# LEDs_-_Schematic.net
KiCad netlist of a schematic drawn in EAGLE
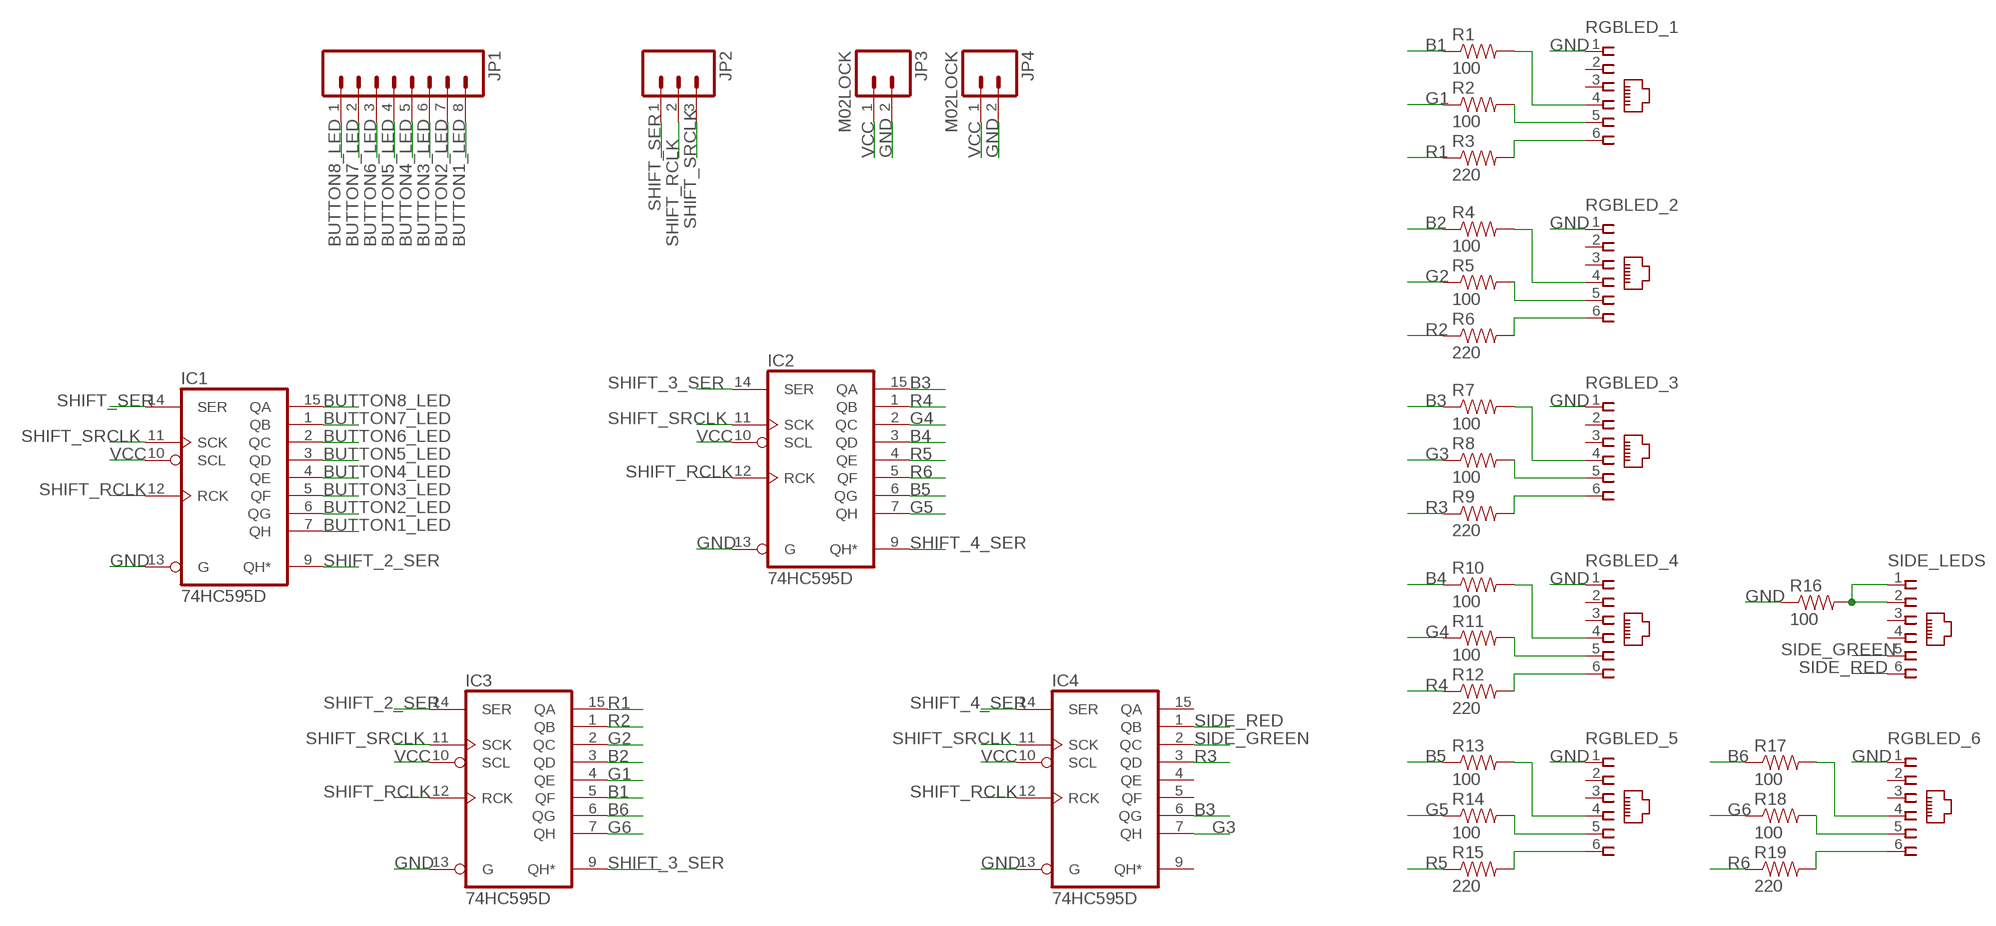
[diagram p0: schematic, sheet 1]

(export (version "E")
  (design (tool "Eeschema 10.0.6"))
  (components
    (comp (ref "IC1")
      (value "74HC595D")
      (footprint "eagle-import:SO16")
      (libsource (lib "eagle-import") (part "74595DHC"))
    )
    (comp (ref "IC2")
      (value "74HC595D")
      (footprint "eagle-import:SO16")
      (libsource (lib "eagle-import") (part "74595DHC"))
    )
    (comp (ref "IC3")
      (value "74HC595D")
      (footprint "eagle-import:SO16")
      (libsource (lib "eagle-import") (part "74595DHC"))
    )
    (comp (ref "IC4")
      (value "74HC595D")
      (footprint "eagle-import:SO16")
      (libsource (lib "eagle-import") (part "74595DHC"))
    )
    (comp (ref "JP1")
      (value "M08LOCK")
      (footprint "eagle-import:1X08_LOCK")
      (libsource (lib "eagle-import") (part "M08LOCK"))
    )
    (comp (ref "JP2")
      (value "M03LOCK")
      (footprint "eagle-import:1X03_LOCK")
      (libsource (lib "eagle-import") (part "M03LOCK"))
    )
    (comp (ref "JP3")
      (value "M02LOCK")
      (footprint "eagle-import:1X02_LOCK")
      (libsource (lib "eagle-import") (part "M02LOCK"))
    )
    (comp (ref "JP4")
      (value "M02LOCK")
      (footprint "eagle-import:1X02_LOCK")
      (libsource (lib "eagle-import") (part "M02LOCK"))
    )
    (comp (ref "R1")
      (value "100")
      (footprint "eagle-import:0603-RES")
      (libsource (lib "eagle-import") (part "RESISTOR0603"))
    )
    (comp (ref "R2")
      (value "100")
      (footprint "eagle-import:0603-RES")
      (libsource (lib "eagle-import") (part "RESISTOR0603"))
    )
    (comp (ref "R3")
      (value "220")
      (footprint "eagle-import:0603-RES")
      (libsource (lib "eagle-import") (part "RESISTOR0603"))
    )
    (comp (ref "R4")
      (value "100")
      (footprint "eagle-import:0603-RES")
      (libsource (lib "eagle-import") (part "RESISTOR0603"))
    )
    (comp (ref "R5")
      (value "100")
      (footprint "eagle-import:0603-RES")
      (libsource (lib "eagle-import") (part "RESISTOR0603"))
    )
    (comp (ref "R6")
      (value "220")
      (footprint "eagle-import:0603-RES")
      (libsource (lib "eagle-import") (part "RESISTOR0603"))
    )
    (comp (ref "R7")
      (value "100")
      (footprint "eagle-import:0603-RES")
      (libsource (lib "eagle-import") (part "RESISTOR0603"))
    )
    (comp (ref "R8")
      (value "100")
      (footprint "eagle-import:0603-RES")
      (libsource (lib "eagle-import") (part "RESISTOR0603"))
    )
    (comp (ref "R9")
      (value "220")
      (footprint "eagle-import:0603-RES")
      (libsource (lib "eagle-import") (part "RESISTOR0603"))
    )
    (comp (ref "R10")
      (value "100")
      (footprint "eagle-import:0603-RES")
      (libsource (lib "eagle-import") (part "RESISTOR0603"))
    )
    (comp (ref "R11")
      (value "100")
      (footprint "eagle-import:0603-RES")
      (libsource (lib "eagle-import") (part "RESISTOR0603"))
    )
    (comp (ref "R12")
      (value "220")
      (footprint "eagle-import:0603-RES")
      (libsource (lib "eagle-import") (part "RESISTOR0603"))
    )
    (comp (ref "R13")
      (value "100")
      (footprint "eagle-import:0603-RES")
      (libsource (lib "eagle-import") (part "RESISTOR0603"))
    )
    (comp (ref "R14")
      (value "100")
      (footprint "eagle-import:0603-RES")
      (libsource (lib "eagle-import") (part "RESISTOR0603"))
    )
    (comp (ref "R15")
      (value "220")
      (footprint "eagle-import:0603-RES")
      (libsource (lib "eagle-import") (part "RESISTOR0603"))
    )
    (comp (ref "R16")
      (value "100")
      (footprint "eagle-import:0603-RES")
      (libsource (lib "eagle-import") (part "RESISTOR0603"))
    )
    (comp (ref "R17")
      (value "100")
      (footprint "eagle-import:0603-RES")
      (libsource (lib "eagle-import") (part "RESISTOR0603"))
    )
    (comp (ref "R18")
      (value "100")
      (footprint "eagle-import:0603-RES")
      (libsource (lib "eagle-import") (part "RESISTOR0603"))
    )
    (comp (ref "R19")
      (value "220")
      (footprint "eagle-import:0603-RES")
      (libsource (lib "eagle-import") (part "RESISTOR0603"))
    )
    (comp (ref "RGBLED_1")
      (value "555165-1")
      (footprint "eagle-import:555165-1")
      (libsource (lib "eagle-import") (part "555165-1"))
    )
    (comp (ref "RGBLED_2")
      (value "555165-1")
      (footprint "eagle-import:555165-1")
      (libsource (lib "eagle-import") (part "555165-1"))
    )
    (comp (ref "RGBLED_3")
      (value "555165-1")
      (footprint "eagle-import:555165-1")
      (libsource (lib "eagle-import") (part "555165-1"))
    )
    (comp (ref "RGBLED_4")
      (value "555165-1")
      (footprint "eagle-import:555165-1")
      (libsource (lib "eagle-import") (part "555165-1"))
    )
    (comp (ref "RGBLED_5")
      (value "555165-1")
      (footprint "eagle-import:555165-1")
      (libsource (lib "eagle-import") (part "555165-1"))
    )
    (comp (ref "RGBLED_6")
      (value "555165-1")
      (footprint "eagle-import:555165-1")
      (libsource (lib "eagle-import") (part "555165-1"))
    )
    (comp (ref "SIDE_LEDS")
      (value "555165-1")
      (footprint "eagle-import:555165-1")
      (libsource (lib "eagle-import") (part "555165-1"))
    )
  )
  (nets
    (net (code "1") (name "/B1") (class "Default")
      (node (ref "IC3") (pin "5") (pinfunction "QF_5") (pintype "tri_state"))
      (node (ref "R1") (pin "1") (pinfunction "1_1") (pintype "passive"))
    )
    (net (code "2") (name "/B2") (class "Default")
      (node (ref "IC3") (pin "3") (pinfunction "QD_3") (pintype "tri_state"))
      (node (ref "R4") (pin "1") (pinfunction "1_1") (pintype "passive"))
    )
    (net (code "3") (name "/B3") (class "Default")
      (node (ref "IC2") (pin "15") (pinfunction "QA_15") (pintype "tri_state"))
      (node (ref "IC4") (pin "6") (pinfunction "QG_6") (pintype "tri_state"))
      (node (ref "R7") (pin "1") (pinfunction "1_1") (pintype "passive"))
    )
    (net (code "4") (name "/B4") (class "Default")
      (node (ref "IC2") (pin "3") (pinfunction "QD_3") (pintype "tri_state"))
      (node (ref "R10") (pin "1") (pinfunction "1_1") (pintype "passive"))
    )
    (net (code "5") (name "/B5") (class "Default")
      (node (ref "IC2") (pin "6") (pinfunction "QG_6") (pintype "tri_state"))
      (node (ref "R13") (pin "1") (pinfunction "1_1") (pintype "passive"))
    )
    (net (code "6") (name "/B6") (class "Default")
      (node (ref "IC3") (pin "6") (pinfunction "QG_6") (pintype "tri_state"))
      (node (ref "R17") (pin "1") (pinfunction "1_1") (pintype "passive"))
    )
    (net (code "7") (name "/BUTTON1_LED") (class "Default")
      (node (ref "IC1") (pin "7") (pinfunction "QH_7") (pintype "tri_state"))
      (node (ref "JP1") (pin "8") (pinfunction "8_8") (pintype "passive"))
    )
    (net (code "8") (name "/BUTTON2_LED") (class "Default")
      (node (ref "IC1") (pin "6") (pinfunction "QG_6") (pintype "tri_state"))
      (node (ref "JP1") (pin "7") (pinfunction "7_7") (pintype "passive"))
    )
    (net (code "9") (name "/BUTTON3_LED") (class "Default")
      (node (ref "IC1") (pin "5") (pinfunction "QF_5") (pintype "tri_state"))
      (node (ref "JP1") (pin "6") (pinfunction "6_6") (pintype "passive"))
    )
    (net (code "10") (name "/BUTTON4_LED") (class "Default")
      (node (ref "IC1") (pin "4") (pinfunction "QE_4") (pintype "tri_state"))
      (node (ref "JP1") (pin "5") (pinfunction "5_5") (pintype "passive"))
    )
    (net (code "11") (name "/BUTTON5_LED") (class "Default")
      (node (ref "IC1") (pin "3") (pinfunction "QD_3") (pintype "tri_state"))
      (node (ref "JP1") (pin "4") (pinfunction "4_4") (pintype "passive"))
    )
    (net (code "12") (name "/BUTTON6_LED") (class "Default")
      (node (ref "IC1") (pin "2") (pinfunction "QC_2") (pintype "tri_state"))
      (node (ref "JP1") (pin "3") (pinfunction "3_3") (pintype "passive"))
    )
    (net (code "13") (name "/BUTTON7_LED") (class "Default")
      (node (ref "IC1") (pin "1") (pinfunction "QB_1") (pintype "tri_state"))
      (node (ref "JP1") (pin "2") (pinfunction "2_2") (pintype "passive"))
    )
    (net (code "14") (name "/BUTTON8_LED") (class "Default")
      (node (ref "IC1") (pin "15") (pinfunction "QA_15") (pintype "tri_state"))
      (node (ref "JP1") (pin "1") (pinfunction "1_1") (pintype "passive"))
    )
    (net (code "15") (name "/G1") (class "Default")
      (node (ref "IC3") (pin "4") (pinfunction "QE_4") (pintype "tri_state"))
      (node (ref "R2") (pin "1") (pinfunction "1_1") (pintype "passive"))
    )
    (net (code "16") (name "/G2") (class "Default")
      (node (ref "IC3") (pin "2") (pinfunction "QC_2") (pintype "tri_state"))
      (node (ref "R5") (pin "1") (pinfunction "1_1") (pintype "passive"))
    )
    (net (code "17") (name "/G3") (class "Default")
      (node (ref "IC4") (pin "7") (pinfunction "QH_7") (pintype "tri_state"))
      (node (ref "R8") (pin "1") (pinfunction "1_1") (pintype "passive"))
    )
    (net (code "18") (name "/G4") (class "Default")
      (node (ref "IC2") (pin "2") (pinfunction "QC_2") (pintype "tri_state"))
      (node (ref "R11") (pin "1") (pinfunction "1_1") (pintype "passive"))
    )
    (net (code "19") (name "/G5") (class "Default")
      (node (ref "IC2") (pin "7") (pinfunction "QH_7") (pintype "tri_state"))
      (node (ref "R14") (pin "1") (pinfunction "1_1") (pintype "passive"))
    )
    (net (code "20") (name "/G6") (class "Default")
      (node (ref "IC3") (pin "7") (pinfunction "QH_7") (pintype "tri_state"))
      (node (ref "R18") (pin "1") (pinfunction "1_1") (pintype "passive"))
    )
    (net (code "21") (name "/GND") (class "Default")
      (node (ref "IC1") (pin "13") (pinfunction "G_13") (pintype "input"))
      (node (ref "IC2") (pin "13") (pinfunction "G_13") (pintype "input"))
      (node (ref "IC3") (pin "13") (pinfunction "G_13") (pintype "input"))
      (node (ref "IC4") (pin "13") (pinfunction "G_13") (pintype "input"))
      (node (ref "JP3") (pin "2") (pinfunction "2_2") (pintype "passive"))
      (node (ref "JP4") (pin "2") (pinfunction "2_2") (pintype "passive"))
      (node (ref "R16") (pin "1") (pinfunction "1_1") (pintype "passive"))
      (node (ref "RGBLED_1") (pin "1") (pinfunction "1_1") (pintype "passive"))
      (node (ref "RGBLED_2") (pin "1") (pinfunction "1_1") (pintype "passive"))
      (node (ref "RGBLED_3") (pin "1") (pinfunction "1_1") (pintype "passive"))
      (node (ref "RGBLED_4") (pin "1") (pinfunction "1_1") (pintype "passive"))
      (node (ref "RGBLED_5") (pin "1") (pinfunction "1_1") (pintype "passive"))
      (node (ref "RGBLED_6") (pin "1") (pinfunction "1_1") (pintype "passive"))
    )
    (net (code "22") (name "/R1") (class "Default")
      (node (ref "IC3") (pin "15") (pinfunction "QA_15") (pintype "tri_state"))
      (node (ref "R3") (pin "1") (pinfunction "1_1") (pintype "passive"))
    )
    (net (code "23") (name "/R2") (class "Default")
      (node (ref "IC3") (pin "1") (pinfunction "QB_1") (pintype "tri_state"))
      (node (ref "R6") (pin "1") (pinfunction "1_1") (pintype "passive"))
    )
    (net (code "24") (name "/R3") (class "Default")
      (node (ref "IC4") (pin "3") (pinfunction "QD_3") (pintype "tri_state"))
      (node (ref "R9") (pin "1") (pinfunction "1_1") (pintype "passive"))
    )
    (net (code "25") (name "/R4") (class "Default")
      (node (ref "IC2") (pin "1") (pinfunction "QB_1") (pintype "tri_state"))
      (node (ref "R12") (pin "1") (pinfunction "1_1") (pintype "passive"))
    )
    (net (code "26") (name "/R5") (class "Default")
      (node (ref "IC2") (pin "4") (pinfunction "QE_4") (pintype "tri_state"))
      (node (ref "R15") (pin "1") (pinfunction "1_1") (pintype "passive"))
    )
    (net (code "27") (name "/R6") (class "Default")
      (node (ref "IC2") (pin "5") (pinfunction "QF_5") (pintype "tri_state"))
      (node (ref "R19") (pin "1") (pinfunction "1_1") (pintype "passive"))
    )
    (net (code "28") (name "/SHIFT_2_SER") (class "Default")
      (node (ref "IC1") (pin "9") (pinfunction "QH*_9") (pintype "tri_state"))
      (node (ref "IC3") (pin "14") (pinfunction "SER_14") (pintype "input"))
    )
    (net (code "29") (name "/SHIFT_3_SER") (class "Default")
      (node (ref "IC2") (pin "14") (pinfunction "SER_14") (pintype "input"))
      (node (ref "IC3") (pin "9") (pinfunction "QH*_9") (pintype "tri_state"))
    )
    (net (code "30") (name "/SHIFT_4_SER") (class "Default")
      (node (ref "IC2") (pin "9") (pinfunction "QH*_9") (pintype "tri_state"))
      (node (ref "IC4") (pin "14") (pinfunction "SER_14") (pintype "input"))
    )
    (net (code "31") (name "/SHIFT_RCLK") (class "Default")
      (node (ref "IC1") (pin "12") (pinfunction "RCK_12") (pintype "input"))
      (node (ref "IC2") (pin "12") (pinfunction "RCK_12") (pintype "input"))
      (node (ref "IC3") (pin "12") (pinfunction "RCK_12") (pintype "input"))
      (node (ref "IC4") (pin "12") (pinfunction "RCK_12") (pintype "input"))
      (node (ref "JP2") (pin "2") (pinfunction "2_2") (pintype "passive"))
    )
    (net (code "32") (name "/SHIFT_SER") (class "Default")
      (node (ref "IC1") (pin "14") (pinfunction "SER_14") (pintype "input"))
      (node (ref "JP2") (pin "1") (pinfunction "1_1") (pintype "passive"))
    )
    (net (code "33") (name "/SHIFT_SRCLK") (class "Default")
      (node (ref "IC1") (pin "11") (pinfunction "SCK_11") (pintype "input"))
      (node (ref "IC2") (pin "11") (pinfunction "SCK_11") (pintype "input"))
      (node (ref "IC3") (pin "11") (pinfunction "SCK_11") (pintype "input"))
      (node (ref "IC4") (pin "11") (pinfunction "SCK_11") (pintype "input"))
      (node (ref "JP2") (pin "3") (pinfunction "3_3") (pintype "passive"))
    )
    (net (code "34") (name "/SIDE_GREEN") (class "Default")
      (node (ref "IC4") (pin "2") (pinfunction "QC_2") (pintype "tri_state"))
      (node (ref "SIDE_LEDS") (pin "5") (pinfunction "5_5") (pintype "passive"))
    )
    (net (code "35") (name "/SIDE_RED") (class "Default")
      (node (ref "IC4") (pin "1") (pinfunction "QB_1") (pintype "tri_state"))
      (node (ref "SIDE_LEDS") (pin "6") (pinfunction "6_6") (pintype "passive"))
    )
    (net (code "36") (name "/VCC") (class "Default")
      (node (ref "IC1") (pin "10") (pinfunction "SCL_10") (pintype "input"))
      (node (ref "IC2") (pin "10") (pinfunction "SCL_10") (pintype "input"))
      (node (ref "IC3") (pin "10") (pinfunction "SCL_10") (pintype "input"))
      (node (ref "IC4") (pin "10") (pinfunction "SCL_10") (pintype "input"))
      (node (ref "JP3") (pin "1") (pinfunction "1_1") (pintype "passive"))
      (node (ref "JP4") (pin "1") (pinfunction "1_1") (pintype "passive"))
    )
    (net (code "37") (name "Net-(R1-Pad2)") (class "Default")
      (node (ref "R1") (pin "2") (pinfunction "2_2") (pintype "passive"))
      (node (ref "RGBLED_1") (pin "4") (pinfunction "4_4") (pintype "passive"))
    )
    (net (code "38") (name "Net-(R2-Pad2)") (class "Default")
      (node (ref "R2") (pin "2") (pinfunction "2_2") (pintype "passive"))
      (node (ref "RGBLED_1") (pin "5") (pinfunction "5_5") (pintype "passive"))
    )
    (net (code "39") (name "Net-(R3-Pad2)") (class "Default")
      (node (ref "R3") (pin "2") (pinfunction "2_2") (pintype "passive"))
      (node (ref "RGBLED_1") (pin "6") (pinfunction "6_6") (pintype "passive"))
    )
    (net (code "40") (name "Net-(R4-Pad2)") (class "Default")
      (node (ref "R4") (pin "2") (pinfunction "2_2") (pintype "passive"))
      (node (ref "RGBLED_2") (pin "4") (pinfunction "4_4") (pintype "passive"))
    )
    (net (code "41") (name "Net-(R5-Pad2)") (class "Default")
      (node (ref "R5") (pin "2") (pinfunction "2_2") (pintype "passive"))
      (node (ref "RGBLED_2") (pin "5") (pinfunction "5_5") (pintype "passive"))
    )
    (net (code "42") (name "Net-(R6-Pad2)") (class "Default")
      (node (ref "R6") (pin "2") (pinfunction "2_2") (pintype "passive"))
      (node (ref "RGBLED_2") (pin "6") (pinfunction "6_6") (pintype "passive"))
    )
    (net (code "43") (name "Net-(R7-Pad2)") (class "Default")
      (node (ref "R7") (pin "2") (pinfunction "2_2") (pintype "passive"))
      (node (ref "RGBLED_3") (pin "4") (pinfunction "4_4") (pintype "passive"))
    )
    (net (code "44") (name "Net-(R8-Pad2)") (class "Default")
      (node (ref "R8") (pin "2") (pinfunction "2_2") (pintype "passive"))
      (node (ref "RGBLED_3") (pin "5") (pinfunction "5_5") (pintype "passive"))
    )
    (net (code "45") (name "Net-(R9-Pad2)") (class "Default")
      (node (ref "R9") (pin "2") (pinfunction "2_2") (pintype "passive"))
      (node (ref "RGBLED_3") (pin "6") (pinfunction "6_6") (pintype "passive"))
    )
    (net (code "46") (name "Net-(R10-Pad2)") (class "Default")
      (node (ref "R10") (pin "2") (pinfunction "2_2") (pintype "passive"))
      (node (ref "RGBLED_4") (pin "4") (pinfunction "4_4") (pintype "passive"))
    )
    (net (code "47") (name "Net-(R11-Pad2)") (class "Default")
      (node (ref "R11") (pin "2") (pinfunction "2_2") (pintype "passive"))
      (node (ref "RGBLED_4") (pin "5") (pinfunction "5_5") (pintype "passive"))
    )
    (net (code "48") (name "Net-(R12-Pad2)") (class "Default")
      (node (ref "R12") (pin "2") (pinfunction "2_2") (pintype "passive"))
      (node (ref "RGBLED_4") (pin "6") (pinfunction "6_6") (pintype "passive"))
    )
    (net (code "49") (name "Net-(R13-Pad2)") (class "Default")
      (node (ref "R13") (pin "2") (pinfunction "2_2") (pintype "passive"))
      (node (ref "RGBLED_5") (pin "4") (pinfunction "4_4") (pintype "passive"))
    )
    (net (code "50") (name "Net-(R14-Pad2)") (class "Default")
      (node (ref "R14") (pin "2") (pinfunction "2_2") (pintype "passive"))
      (node (ref "RGBLED_5") (pin "5") (pinfunction "5_5") (pintype "passive"))
    )
    (net (code "51") (name "Net-(R15-Pad2)") (class "Default")
      (node (ref "R15") (pin "2") (pinfunction "2_2") (pintype "passive"))
      (node (ref "RGBLED_5") (pin "6") (pinfunction "6_6") (pintype "passive"))
    )
    (net (code "52") (name "Net-(R16-Pad2)") (class "Default")
      (node (ref "R16") (pin "2") (pinfunction "2_2") (pintype "passive"))
      (node (ref "SIDE_LEDS") (pin "1") (pinfunction "1_1") (pintype "passive"))
      (node (ref "SIDE_LEDS") (pin "2") (pinfunction "2_2") (pintype "passive"))
    )
    (net (code "53") (name "Net-(R17-Pad2)") (class "Default")
      (node (ref "R17") (pin "2") (pinfunction "2_2") (pintype "passive"))
      (node (ref "RGBLED_6") (pin "4") (pinfunction "4_4") (pintype "passive"))
    )
    (net (code "54") (name "Net-(R18-Pad2)") (class "Default")
      (node (ref "R18") (pin "2") (pinfunction "2_2") (pintype "passive"))
      (node (ref "RGBLED_6") (pin "5") (pinfunction "5_5") (pintype "passive"))
    )
    (net (code "55") (name "Net-(R19-Pad2)") (class "Default")
      (node (ref "R19") (pin "2") (pinfunction "2_2") (pintype "passive"))
      (node (ref "RGBLED_6") (pin "6") (pinfunction "6_6") (pintype "passive"))
    )
    (net (code "56") (name "unconnected-(IC4A-QA-Pad15)") (class "Default")
      (node (ref "IC4") (pin "15") (pinfunction "QA_15") (pintype "tri_state"))
    )
    (net (code "57") (name "unconnected-(IC4A-QE-Pad4)") (class "Default")
      (node (ref "IC4") (pin "4") (pinfunction "QE_4") (pintype "tri_state"))
    )
    (net (code "58") (name "unconnected-(IC4A-QF-Pad5)") (class "Default")
      (node (ref "IC4") (pin "5") (pinfunction "QF_5") (pintype "tri_state"))
    )
    (net (code "59") (name "unconnected-(IC4A-QH*-Pad9)") (class "Default")
      (node (ref "IC4") (pin "9") (pinfunction "QH*_9") (pintype "tri_state"))
    )
    (net (code "60") (name "unconnected-(RGBLED_1-Pad2)") (class "Default")
      (node (ref "RGBLED_1") (pin "2") (pinfunction "2_2") (pintype "passive"))
    )
    (net (code "61") (name "unconnected-(RGBLED_1-Pad3)") (class "Default")
      (node (ref "RGBLED_1") (pin "3") (pinfunction "3_3") (pintype "passive"))
    )
    (net (code "62") (name "unconnected-(RGBLED_2-Pad2)") (class "Default")
      (node (ref "RGBLED_2") (pin "2") (pinfunction "2_2") (pintype "passive"))
    )
    (net (code "63") (name "unconnected-(RGBLED_2-Pad3)") (class "Default")
      (node (ref "RGBLED_2") (pin "3") (pinfunction "3_3") (pintype "passive"))
    )
    (net (code "64") (name "unconnected-(RGBLED_3-Pad2)") (class "Default")
      (node (ref "RGBLED_3") (pin "2") (pinfunction "2_2") (pintype "passive"))
    )
    (net (code "65") (name "unconnected-(RGBLED_3-Pad3)") (class "Default")
      (node (ref "RGBLED_3") (pin "3") (pinfunction "3_3") (pintype "passive"))
    )
    (net (code "66") (name "unconnected-(RGBLED_4-Pad2)") (class "Default")
      (node (ref "RGBLED_4") (pin "2") (pinfunction "2_2") (pintype "passive"))
    )
    (net (code "67") (name "unconnected-(RGBLED_4-Pad3)") (class "Default")
      (node (ref "RGBLED_4") (pin "3") (pinfunction "3_3") (pintype "passive"))
    )
    (net (code "68") (name "unconnected-(RGBLED_5-Pad2)") (class "Default")
      (node (ref "RGBLED_5") (pin "2") (pinfunction "2_2") (pintype "passive"))
    )
    (net (code "69") (name "unconnected-(RGBLED_5-Pad3)") (class "Default")
      (node (ref "RGBLED_5") (pin "3") (pinfunction "3_3") (pintype "passive"))
    )
    (net (code "70") (name "unconnected-(RGBLED_6-Pad2)") (class "Default")
      (node (ref "RGBLED_6") (pin "2") (pinfunction "2_2") (pintype "passive"))
    )
    (net (code "71") (name "unconnected-(RGBLED_6-Pad3)") (class "Default")
      (node (ref "RGBLED_6") (pin "3") (pinfunction "3_3") (pintype "passive"))
    )
    (net (code "72") (name "unconnected-(SIDE_LEDS-Pad3)") (class "Default")
      (node (ref "SIDE_LEDS") (pin "3") (pinfunction "3_3") (pintype "passive"))
    )
    (net (code "73") (name "unconnected-(SIDE_LEDS-Pad4)") (class "Default")
      (node (ref "SIDE_LEDS") (pin "4") (pinfunction "4_4") (pintype "passive"))
    )
  )
)
